# Main.net
KiCad netlist of a schematic drawn in Altium Designer
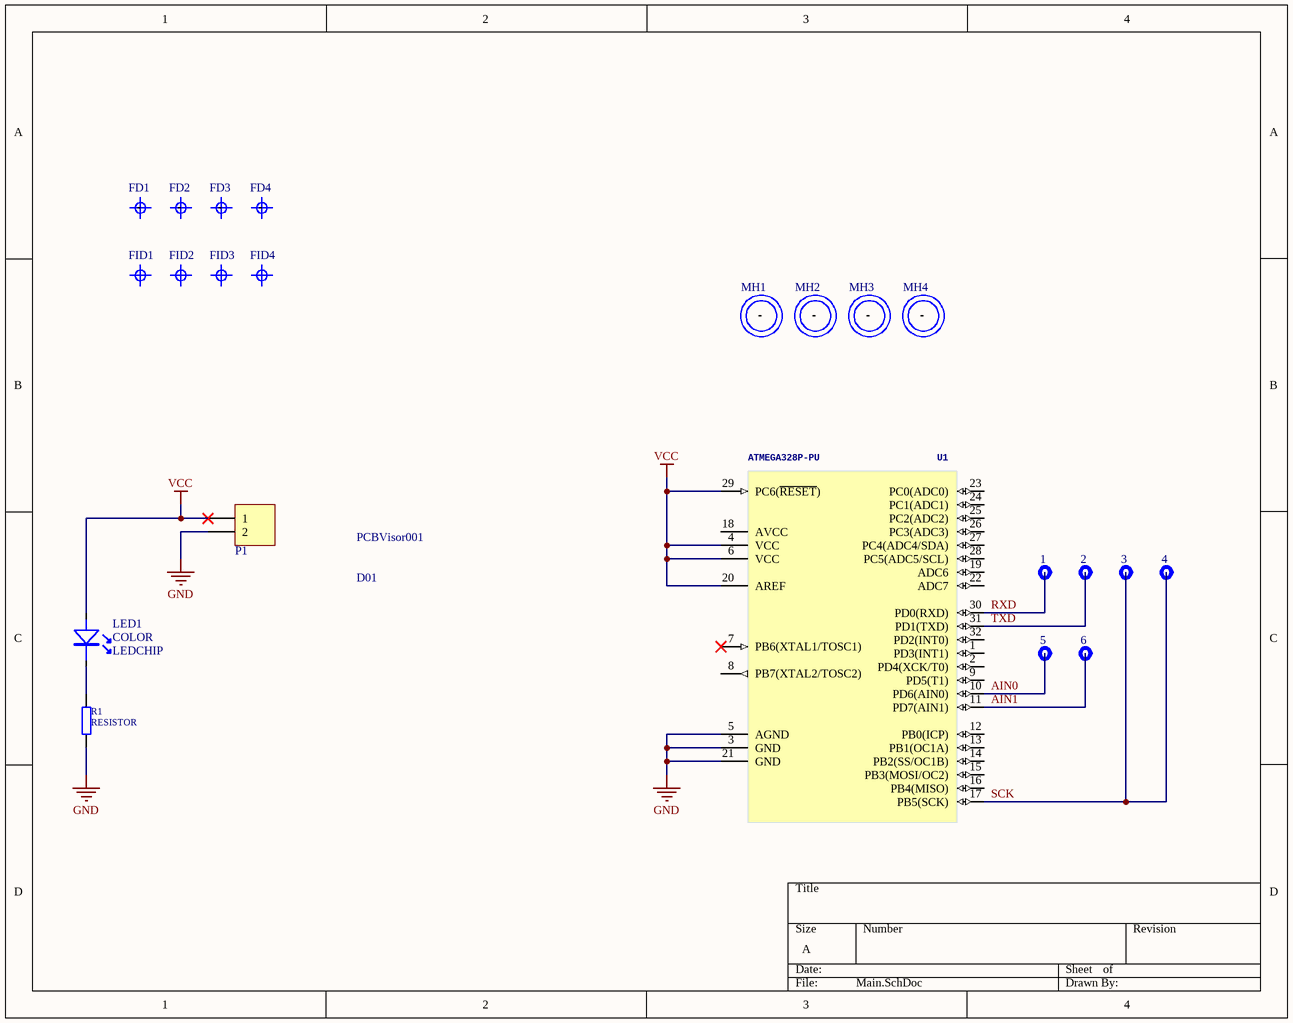
[diagram p0: Main.SchDoc]

(export (version "E")
  (design (tool "Eeschema 10.0.6"))
  (components
    (comp (ref "1") (value "Test Point") (footprint "TEST_POINT") (libsource (lib "MyIntLib") (part "TP")))
    (comp (ref "2") (value "Test Point") (footprint "TEST_POINT") (libsource (lib "MyIntLib") (part "TP")))
    (comp (ref "3") (value "Test Point") (footprint "TEST_POINT") (libsource (lib "MyIntLib") (part "TP")))
    (comp (ref "4") (value "Test Point") (footprint "TEST_POINT") (libsource (lib "MyIntLib") (part "TP")))
    (comp (ref "5") (value "Test Point") (footprint "TEST_POINT") (libsource (lib "MyIntLib") (part "TP")))
    (comp (ref "6") (value "Test Point") (footprint "TEST_POINT") (libsource (lib "MyIntLib") (part "TP")))
    (comp (ref "FD1")
      (value "Global Fiducial Mark")
      (footprint "FIDUCIAL_0.8MM")
      (libsource (lib "MyIntLib") (part "FD"))
    )
    (comp (ref "FD2")
      (value "Global Fiducial Mark")
      (footprint "FIDUCIAL_0.8MM")
      (libsource (lib "MyIntLib") (part "FD"))
    )
    (comp (ref "FD3")
      (value "Global Fiducial Mark")
      (footprint "FIDUCIAL_0.8MM")
      (libsource (lib "MyIntLib") (part "FD"))
    )
    (comp (ref "FD4")
      (value "Global Fiducial Mark")
      (footprint "FIDUCIAL_0.8MM")
      (libsource (lib "MyIntLib") (part "FD"))
    )
    (comp (ref "FID1")
      (value "Global Fiducial Mark")
      (footprint "FIDUCIAL_0.8MM")
      (libsource (lib "MyIntLib") (part "FID"))
    )
    (comp (ref "FID2")
      (value "Global Fiducial Mark")
      (footprint "FIDUCIAL_0.8MM")
      (libsource (lib "MyIntLib") (part "FID"))
    )
    (comp (ref "FID3")
      (value "Global Fiducial Mark")
      (footprint "FIDUCIAL_0.8MM")
      (libsource (lib "MyIntLib") (part "FID"))
    )
    (comp (ref "FID4")
      (value "Global Fiducial Mark")
      (footprint "FIDUCIAL_0.8MM")
      (libsource (lib "MyIntLib") (part "FID"))
    )
    (comp (ref "LED1")
      (value "LEDCHIP")
      (footprint "CHIP-LED0603")
      (description "SMD lamp beads")
      (fields (field (name "ALTIUM_VALUE") "COLOR"))
      (libsource (lib "Mastermind Devices") (part "LEDCHIP"))
    )
    (comp (ref "MH1")
      (value "Mounting Hole")
      (footprint "MOUNTING_HOLE_3MM")
      (libsource (lib "MyIntLib") (part "MH"))
    )
    (comp (ref "MH2")
      (value "Mounting Hole")
      (footprint "MOUNTING_HOLE_3MM")
      (libsource (lib "MyIntLib") (part "MH"))
    )
    (comp (ref "MH3")
      (value "Mounting Hole")
      (footprint "MOUNTING_HOLE_3MM")
      (libsource (lib "MyIntLib") (part "MH"))
    )
    (comp (ref "MH4")
      (value "Mounting Hole")
      (footprint "MOUNTING_HOLE_3MM")
      (libsource (lib "MyIntLib") (part "MH"))
    )
    (comp (ref "P1")
      (value "Header 2")
      (footprint "JST-PH-2PIN-2.54-THM")
      (description "Header, 2-Pin")
      (fields (field (name "PUBLISHER") "Altium Limited"))
      (libsource (lib "Mastermind Devices") (part "JST-PH-2PIN-2.54-THM"))
    )
    (comp (ref "R1")
      (value "RESISTOR")
      (footprint "R0603")
      (description "Resistor ?K ±0.1% 0.1W")
      (libsource (lib "Mastermind Devices") (part "RESISTOR"))
    )
    (comp (ref "U1")
      (value "ATMEGA328P-PU")
      (footprint "TQFP32-08")
      (libsource (lib "Mastermind Devices") (part "ATMEGA328P-PU"))
    )
  )
  (nets
    (net (code "1") (name "/AIN0") (class "Default")
      (node (ref "5") (pin "1") (pintype "passive"))
      (node (ref "U1") (pin "10") (pinfunction "PD6(AIN0)_10") (pintype "bidirectional"))
    )
    (net (code "2") (name "/AIN1") (class "Default")
      (node (ref "6") (pin "1") (pintype "passive"))
      (node (ref "U1") (pin "11") (pinfunction "PD7(AIN1)_11") (pintype "bidirectional"))
    )
    (net (code "3") (name "/RXD") (class "Default")
      (node (ref "1") (pin "1") (pintype "passive"))
      (node (ref "U1") (pin "30") (pinfunction "PD0(RXD)_30") (pintype "bidirectional"))
    )
    (net (code "4") (name "/SCK") (class "Default")
      (node (ref "3") (pin "1") (pintype "passive"))
      (node (ref "4") (pin "1") (pintype "passive"))
      (node (ref "U1") (pin "17") (pinfunction "PB5(SCK)_17") (pintype "bidirectional"))
    )
    (net (code "5") (name "/TXD") (class "Default")
      (node (ref "2") (pin "1") (pintype "passive"))
      (node (ref "U1") (pin "31") (pinfunction "PD1(TXD)_31") (pintype "bidirectional"))
    )
    (net (code "6") (name "GND") (class "Default")
      (node (ref "P1") (pin "2") (pinfunction "2_2") (pintype "passive"))
      (node (ref "R1") (pin "2") (pinfunction "2_2") (pintype "passive"))
      (node (ref "U1") (pin "21") (pinfunction "GND_21") (pintype "passive"))
      (node (ref "U1") (pin "3") (pinfunction "GND_3") (pintype "passive"))
      (node (ref "U1") (pin "5") (pinfunction "AGND_5") (pintype "passive"))
    )
    (net (code "7") (name "Net-(LED1-K)") (class "Default")
      (node (ref "LED1") (pin "C") (pinfunction "K_C") (pintype "passive"))
      (node (ref "R1") (pin "1") (pinfunction "1_1") (pintype "passive"))
    )
    (net (code "8") (name "VCC") (class "Default")
      (node (ref "LED1") (pin "A") (pinfunction "A_A") (pintype "passive"))
      (node (ref "P1") (pin "1") (pinfunction "1_1") (pintype "passive"))
      (node (ref "U1") (pin "20") (pinfunction "AREF_20") (pintype "passive"))
      (node (ref "U1") (pin "29") (pinfunction "PC6(~{RESET})_29") (pintype "input"))
      (node (ref "U1") (pin "4") (pinfunction "VCC_4") (pintype "passive"))
      (node (ref "U1") (pin "6") (pinfunction "VCC_6") (pintype "passive"))
    )
    (net (code "9") (name "unconnected-(FD1-Pad0)") (class "Default")
      (node (ref "FD1") (pin "0") (pinfunction "0_0") (pintype "passive"))
    )
    (net (code "10") (name "unconnected-(FD2-Pad0)") (class "Default")
      (node (ref "FD2") (pin "0") (pinfunction "0_0") (pintype "passive"))
    )
    (net (code "11") (name "unconnected-(FD3-Pad0)") (class "Default")
      (node (ref "FD3") (pin "0") (pinfunction "0_0") (pintype "passive"))
    )
    (net (code "12") (name "unconnected-(FD4-Pad0)") (class "Default")
      (node (ref "FD4") (pin "0") (pinfunction "0_0") (pintype "passive"))
    )
    (net (code "13") (name "unconnected-(MH1-Pad0)") (class "Default")
      (node (ref "MH1") (pin "0") (pinfunction "0_0") (pintype "passive"))
    )
    (net (code "14") (name "unconnected-(MH2-Pad0)") (class "Default")
      (node (ref "MH2") (pin "0") (pinfunction "0_0") (pintype "passive"))
    )
    (net (code "15") (name "unconnected-(MH3-Pad0)") (class "Default")
      (node (ref "MH3") (pin "0") (pinfunction "0_0") (pintype "passive"))
    )
    (net (code "16") (name "unconnected-(MH4-Pad0)") (class "Default")
      (node (ref "MH4") (pin "0") (pinfunction "0_0") (pintype "passive"))
    )
    (net (code "17") (name "unconnected-(U1-ADC6-Pad19)") (class "Default")
      (node (ref "U1") (pin "19") (pinfunction "ADC6_19") (pintype "bidirectional"))
    )
    (net (code "18") (name "unconnected-(U1-ADC7-Pad22)") (class "Default")
      (node (ref "U1") (pin "22") (pinfunction "ADC7_22") (pintype "bidirectional"))
    )
    (net (code "19") (name "unconnected-(U1-AVCC-Pad18)") (class "Default")
      (node (ref "U1") (pin "18") (pinfunction "AVCC_18") (pintype "passive"))
    )
    (net (code "20") (name "unconnected-(U1-PB0(ICP)-Pad12)") (class "Default")
      (node (ref "U1") (pin "12") (pinfunction "PB0(ICP)_12") (pintype "bidirectional"))
    )
    (net (code "21") (name "unconnected-(U1-PB1(OC1A)-Pad13)") (class "Default")
      (node (ref "U1") (pin "13") (pinfunction "PB1(OC1A)_13") (pintype "bidirectional"))
    )
    (net (code "22") (name "unconnected-(U1-PB2(SS{slash}OC1B)-Pad14)") (class "Default")
      (node (ref "U1") (pin "14") (pinfunction "PB2(SS/OC1B)_14") (pintype "bidirectional"))
    )
    (net (code "23") (name "unconnected-(U1-PB3(MOSI{slash}OC2)-Pad15)") (class "Default")
      (node (ref "U1") (pin "15") (pinfunction "PB3(MOSI/OC2)_15") (pintype "bidirectional"))
    )
    (net (code "24") (name "unconnected-(U1-PB4(MISO)-Pad16)") (class "Default")
      (node (ref "U1") (pin "16") (pinfunction "PB4(MISO)_16") (pintype "bidirectional"))
    )
    (net (code "25") (name "unconnected-(U1-PB6(XTAL1{slash}TOSC1)-Pad7)") (class "Default")
      (node (ref "U1") (pin "7") (pinfunction "PB6(XTAL1/TOSC1)_7") (pintype "input+no_connect"))
    )
    (net (code "26") (name "unconnected-(U1-PB7(XTAL2{slash}TOSC2)-Pad8)") (class "Default")
      (node (ref "U1") (pin "8") (pinfunction "PB7(XTAL2/TOSC2)_8") (pintype "output"))
    )
    (net (code "27") (name "unconnected-(U1-PC0(ADC0)-Pad23)") (class "Default")
      (node (ref "U1") (pin "23") (pinfunction "PC0(ADC0)_23") (pintype "bidirectional"))
    )
    (net (code "28") (name "unconnected-(U1-PC1(ADC1)-Pad24)") (class "Default")
      (node (ref "U1") (pin "24") (pinfunction "PC1(ADC1)_24") (pintype "bidirectional"))
    )
    (net (code "29") (name "unconnected-(U1-PC2(ADC2)-Pad25)") (class "Default")
      (node (ref "U1") (pin "25") (pinfunction "PC2(ADC2)_25") (pintype "bidirectional"))
    )
    (net (code "30") (name "unconnected-(U1-PC3(ADC3)-Pad26)") (class "Default")
      (node (ref "U1") (pin "26") (pinfunction "PC3(ADC3)_26") (pintype "bidirectional"))
    )
    (net (code "31") (name "unconnected-(U1-PC4(ADC4{slash}SDA)-Pad27)") (class "Default")
      (node (ref "U1") (pin "27") (pinfunction "PC4(ADC4/SDA)_27") (pintype "bidirectional"))
    )
    (net (code "32") (name "unconnected-(U1-PC5(ADC5{slash}SCL)-Pad28)") (class "Default")
      (node (ref "U1") (pin "28") (pinfunction "PC5(ADC5/SCL)_28") (pintype "bidirectional"))
    )
    (net (code "33") (name "unconnected-(U1-PD2(INT0)-Pad32)") (class "Default")
      (node (ref "U1") (pin "32") (pinfunction "PD2(INT0)_32") (pintype "bidirectional"))
    )
    (net (code "34") (name "unconnected-(U1-PD3(INT1)-Pad1)") (class "Default")
      (node (ref "U1") (pin "1") (pinfunction "PD3(INT1)_1") (pintype "bidirectional"))
    )
    (net (code "35") (name "unconnected-(U1-PD4(XCK{slash}T0)-Pad2)") (class "Default")
      (node (ref "U1") (pin "2") (pinfunction "PD4(XCK/T0)_2") (pintype "bidirectional"))
    )
    (net (code "36") (name "unconnected-(U1-PD5(T1)-Pad9)") (class "Default")
      (node (ref "U1") (pin "9") (pinfunction "PD5(T1)_9") (pintype "bidirectional"))
    )
  )
)
